# AdaptadorUSB.net
KiCad netlist of a schematic drawn in Altium Designer
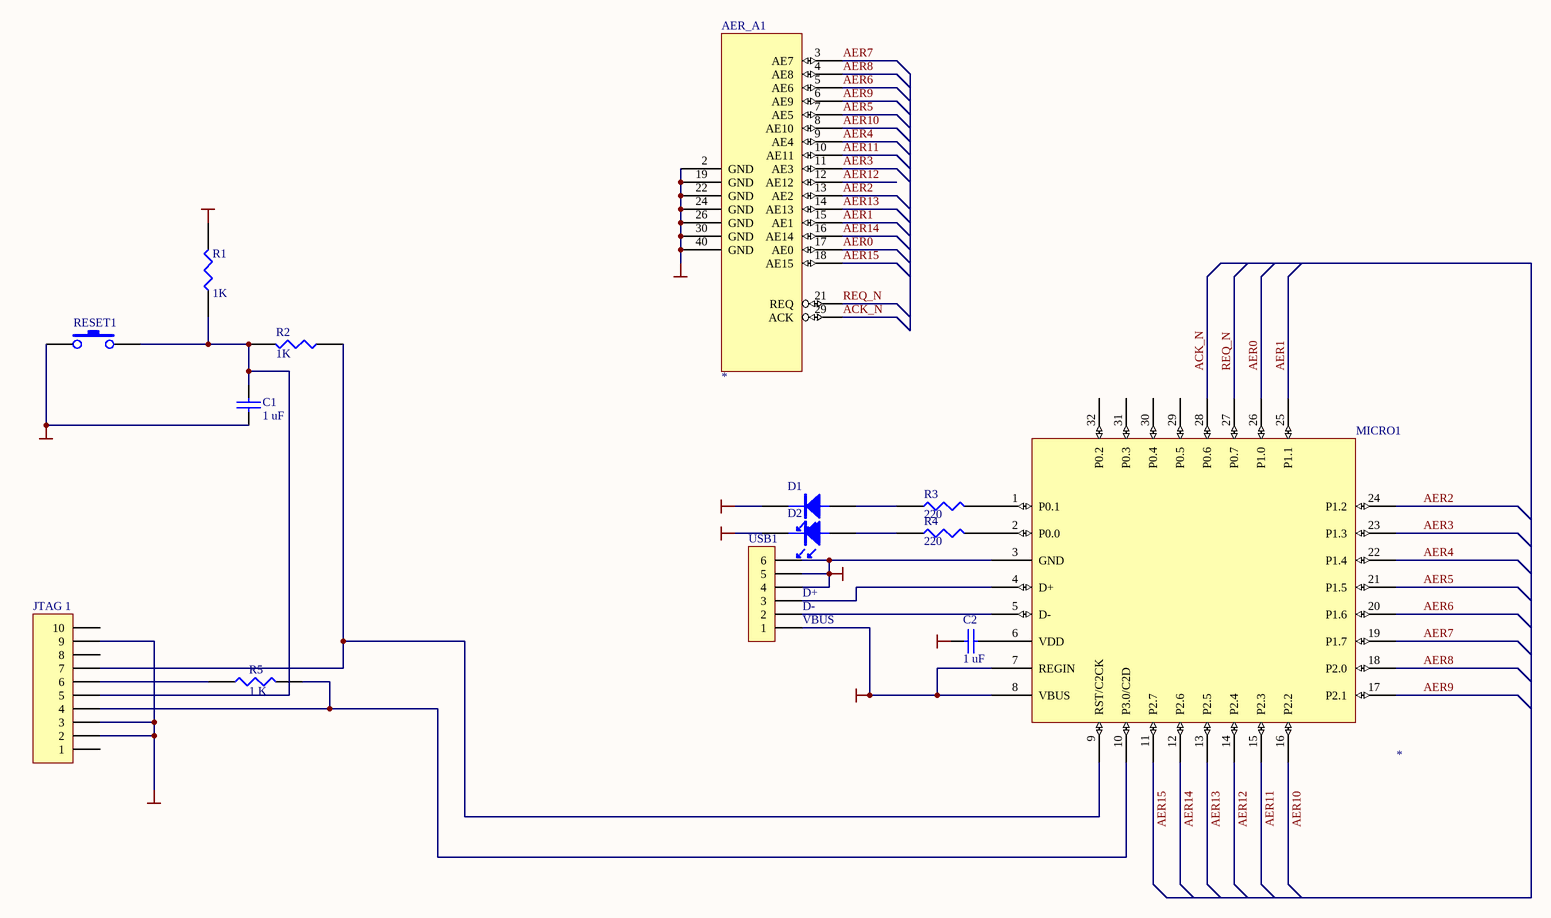
[diagram p0: AdaptadorUSB.SchDoc]

(export (version "E")
  (design (tool "Eeschema 10.0.6"))
  (components
    (comp (ref "AER_A1") (value "*") (footprint "IDC-40") (libsource (lib "Schlib1") (part "CON_AER1")))
    (comp (ref "C1")
      (value "1 uF")
      (footprint "CAP 10")
      (description "Capacitor")
      (libsource (lib "*") (part "CAP"))
    )
    (comp (ref "C2")
      (value "1 uF")
      (footprint "CAP 10")
      (description "Capacitor")
      (libsource (lib "*") (part "CAP"))
    )
    (comp (ref "D1") (value "~") (footprint "LED") (libsource (lib "*") (part "LED")))
    (comp (ref "D2") (value "~") (footprint "LED") (libsource (lib "*") (part "LED")))
    (comp (ref "JTAG 1")
      (value "~")
      (footprint "IDC-10")
      (description "Connector")
      (libsource (lib "*") (part "CON10"))
    )
    (comp (ref "MICRO1") (value "*") (footprint "LQFP-32") (libsource (lib "Schlib1") (part "C8051F320")))
    (comp (ref "R1") (value "1K") (footprint "AXIAL-0.4") (libsource (lib "*") (part "RES1")))
    (comp (ref "R2") (value "1K") (footprint "AXIAL-0.4") (libsource (lib "*") (part "RES1")))
    (comp (ref "R3") (value "220") (footprint "AXIAL-0.4") (libsource (lib "*") (part "RES1")))
    (comp (ref "R4") (value "220") (footprint "AXIAL-0.4") (libsource (lib "*") (part "RES1")))
    (comp (ref "R5") (value "1 K") (footprint "AXIAL-0.4") (libsource (lib "*") (part "RES1")))
    (comp (ref "RESET1") (value "~") (footprint "SIP-2") (libsource (lib "*") (part "SW-PB")))
    (comp (ref "USB1")
      (value "~")
      (footprint "USB_CON")
      (description "Connector")
      (libsource (lib "*") (part "CON6"))
    )
  )
  (nets
    (net (code "1") (name "/ACK_N") (class "Default")
      (node (ref "AER_A1") (pin "29") (pinfunction "ACK_29") (pintype "bidirectional"))
      (node (ref "MICRO1") (pin "28") (pinfunction "P0.6_28") (pintype "bidirectional"))
    )
    (net (code "2") (name "/AER0") (class "Default")
      (node (ref "AER_A1") (pin "17") (pinfunction "AE0_17") (pintype "bidirectional"))
      (node (ref "MICRO1") (pin "26") (pinfunction "P1.0_26") (pintype "bidirectional"))
    )
    (net (code "3") (name "/AER1") (class "Default")
      (node (ref "AER_A1") (pin "15") (pinfunction "AE1_15") (pintype "bidirectional"))
      (node (ref "MICRO1") (pin "25") (pinfunction "P1.1_25") (pintype "bidirectional"))
    )
    (net (code "4") (name "/AER2") (class "Default")
      (node (ref "AER_A1") (pin "13") (pinfunction "AE2_13") (pintype "bidirectional"))
      (node (ref "MICRO1") (pin "24") (pinfunction "P1.2_24") (pintype "bidirectional"))
    )
    (net (code "5") (name "/AER3") (class "Default")
      (node (ref "AER_A1") (pin "11") (pinfunction "AE3_11") (pintype "bidirectional"))
      (node (ref "MICRO1") (pin "23") (pinfunction "P1.3_23") (pintype "bidirectional"))
    )
    (net (code "6") (name "/AER4") (class "Default")
      (node (ref "AER_A1") (pin "9") (pinfunction "AE4_9") (pintype "bidirectional"))
      (node (ref "MICRO1") (pin "22") (pinfunction "P1.4_22") (pintype "bidirectional"))
    )
    (net (code "7") (name "/AER5") (class "Default")
      (node (ref "AER_A1") (pin "7") (pinfunction "AE5_7") (pintype "bidirectional"))
      (node (ref "MICRO1") (pin "21") (pinfunction "P1.5_21") (pintype "bidirectional"))
    )
    (net (code "8") (name "/AER6") (class "Default")
      (node (ref "AER_A1") (pin "5") (pinfunction "AE6_5") (pintype "bidirectional"))
      (node (ref "MICRO1") (pin "20") (pinfunction "P1.6_20") (pintype "bidirectional"))
    )
    (net (code "9") (name "/AER7") (class "Default")
      (node (ref "AER_A1") (pin "3") (pinfunction "AE7_3") (pintype "bidirectional"))
      (node (ref "MICRO1") (pin "19") (pinfunction "P1.7_19") (pintype "bidirectional"))
    )
    (net (code "10") (name "/AER8") (class "Default")
      (node (ref "AER_A1") (pin "4") (pinfunction "AE8_4") (pintype "bidirectional"))
      (node (ref "MICRO1") (pin "18") (pinfunction "P2.0_18") (pintype "bidirectional"))
    )
    (net (code "11") (name "/AER9") (class "Default")
      (node (ref "AER_A1") (pin "6") (pinfunction "AE9_6") (pintype "bidirectional"))
      (node (ref "MICRO1") (pin "17") (pinfunction "P2.1_17") (pintype "bidirectional"))
    )
    (net (code "12") (name "/AER10") (class "Default")
      (node (ref "AER_A1") (pin "8") (pinfunction "AE10_8") (pintype "bidirectional"))
      (node (ref "MICRO1") (pin "16") (pinfunction "P2.2_16") (pintype "bidirectional"))
    )
    (net (code "13") (name "/AER11") (class "Default")
      (node (ref "AER_A1") (pin "10") (pinfunction "AE11_10") (pintype "bidirectional"))
      (node (ref "MICRO1") (pin "15") (pinfunction "P2.3_15") (pintype "bidirectional"))
    )
    (net (code "14") (name "/AER12") (class "Default")
      (node (ref "AER_A1") (pin "12") (pinfunction "AE12_12") (pintype "bidirectional"))
      (node (ref "MICRO1") (pin "14") (pinfunction "P2.4_14") (pintype "bidirectional"))
    )
    (net (code "15") (name "/AER13") (class "Default")
      (node (ref "AER_A1") (pin "14") (pinfunction "AE13_14") (pintype "bidirectional"))
      (node (ref "MICRO1") (pin "13") (pinfunction "P2.5_13") (pintype "bidirectional"))
    )
    (net (code "16") (name "/AER14") (class "Default")
      (node (ref "AER_A1") (pin "16") (pinfunction "AE14_16") (pintype "bidirectional"))
      (node (ref "MICRO1") (pin "12") (pinfunction "P2.6_12") (pintype "bidirectional"))
    )
    (net (code "17") (name "/AER15") (class "Default")
      (node (ref "AER_A1") (pin "18") (pinfunction "AE15_18") (pintype "bidirectional"))
      (node (ref "MICRO1") (pin "11") (pinfunction "P2.7_11") (pintype "bidirectional"))
    )
    (net (code "18") (name "/REQ_N") (class "Default")
      (node (ref "AER_A1") (pin "21") (pinfunction "REQ_21") (pintype "bidirectional"))
      (node (ref "MICRO1") (pin "27") (pinfunction "P0.7_27") (pintype "bidirectional"))
    )
    (net (code "19") (name "GND") (class "Default")
      (node (ref "AER_A1") (pin "19") (pinfunction "GND_19") (pintype "power_in"))
      (node (ref "AER_A1") (pin "2") (pinfunction "GND_2") (pintype "power_in"))
      (node (ref "AER_A1") (pin "22") (pinfunction "GND_22") (pintype "power_in"))
      (node (ref "AER_A1") (pin "24") (pinfunction "GND_24") (pintype "power_in"))
      (node (ref "AER_A1") (pin "26") (pinfunction "GND_26") (pintype "power_in"))
      (node (ref "AER_A1") (pin "30") (pinfunction "GND_30") (pintype "power_in"))
      (node (ref "AER_A1") (pin "40") (pinfunction "GND_40") (pintype "power_in"))
      (node (ref "C1") (pin "2") (pinfunction "2_2") (pintype "passive"))
      (node (ref "C2") (pin "1") (pinfunction "1_1") (pintype "passive"))
      (node (ref "D1") (pin "K") (pinfunction "2_K") (pintype "passive"))
      (node (ref "D2") (pin "K") (pinfunction "2_K") (pintype "passive"))
      (node (ref "JTAG 1") (pin "2") (pinfunction "2_2") (pintype "passive"))
      (node (ref "JTAG 1") (pin "3") (pinfunction "3_3") (pintype "passive"))
      (node (ref "JTAG 1") (pin "9") (pinfunction "9_9") (pintype "passive"))
      (node (ref "MICRO1") (pin "3") (pinfunction "GND_3") (pintype "power_in"))
      (node (ref "RESET1") (pin "1") (pinfunction "1_1") (pintype "passive"))
      (node (ref "USB1") (pin "4") (pinfunction "4_4") (pintype "passive"))
      (node (ref "USB1") (pin "5") (pinfunction "5_5") (pintype "passive"))
      (node (ref "USB1") (pin "6") (pinfunction "6_6") (pintype "passive"))
    )
    (net (code "20") (name "Net-(C1-Pad1)") (class "Default")
      (node (ref "C1") (pin "1") (pinfunction "1_1") (pintype "passive"))
      (node (ref "JTAG 1") (pin "5") (pinfunction "5_5") (pintype "passive"))
      (node (ref "R1") (pin "1") (pinfunction "1_1") (pintype "passive"))
      (node (ref "R2") (pin "2") (pinfunction "2_2") (pintype "passive"))
      (node (ref "RESET1") (pin "2") (pinfunction "2_2") (pintype "passive"))
    )
    (net (code "21") (name "Net-(D1-1)") (class "Default")
      (node (ref "D1") (pin "A") (pinfunction "1_A") (pintype "passive"))
      (node (ref "R3") (pin "1") (pinfunction "1_1") (pintype "passive"))
    )
    (net (code "22") (name "Net-(D2-1)") (class "Default")
      (node (ref "D2") (pin "A") (pinfunction "1_A") (pintype "passive"))
      (node (ref "R4") (pin "1") (pinfunction "1_1") (pintype "passive"))
    )
    (net (code "23") (name "Net-(JTAG 1-Pad6)") (class "Default")
      (node (ref "JTAG 1") (pin "6") (pinfunction "6_6") (pintype "passive"))
      (node (ref "R5") (pin "1") (pinfunction "1_1") (pintype "passive"))
    )
    (net (code "24") (name "Net-(MICRO1-D+)") (class "Default")
      (node (ref "MICRO1") (pin "4") (pinfunction "D+_4") (pintype "bidirectional"))
      (node (ref "USB1") (pin "3") (pinfunction "3_3") (pintype "passive"))
    )
    (net (code "25") (name "Net-(MICRO1-D-)") (class "Default")
      (node (ref "MICRO1") (pin "5") (pinfunction "D-_5") (pintype "bidirectional"))
      (node (ref "USB1") (pin "2") (pinfunction "2_2") (pintype "passive"))
    )
    (net (code "26") (name "Net-(MICRO1-P0.0)") (class "Default")
      (node (ref "MICRO1") (pin "2") (pinfunction "P0.0_2") (pintype "bidirectional"))
      (node (ref "R4") (pin "2") (pinfunction "2_2") (pintype "passive"))
    )
    (net (code "27") (name "Net-(MICRO1-P0.1)") (class "Default")
      (node (ref "MICRO1") (pin "1") (pinfunction "P0.1_1") (pintype "bidirectional"))
      (node (ref "R3") (pin "2") (pinfunction "2_2") (pintype "passive"))
    )
    (net (code "28") (name "Net-(MICRO1-P3.0{slash}C2D)") (class "Default")
      (node (ref "JTAG 1") (pin "4") (pinfunction "4_4") (pintype "passive"))
      (node (ref "MICRO1") (pin "10") (pinfunction "P3.0/C2D_10") (pintype "bidirectional"))
      (node (ref "R5") (pin "2") (pinfunction "2_2") (pintype "passive"))
    )
    (net (code "29") (name "Net-(MICRO1-RST{slash}C2CK)") (class "Default")
      (node (ref "JTAG 1") (pin "7") (pinfunction "7_7") (pintype "passive"))
      (node (ref "MICRO1") (pin "9") (pinfunction "RST/C2CK_9") (pintype "bidirectional"))
      (node (ref "R2") (pin "1") (pinfunction "1_1") (pintype "passive"))
    )
    (net (code "30") (name "Net-(MICRO1-VDD)") (class "Default")
      (node (ref "C2") (pin "2") (pinfunction "2_2") (pintype "passive"))
      (node (ref "MICRO1") (pin "6") (pinfunction "VDD_6") (pintype "power_in"))
    )
    (net (code "31") (name "VCC_3.3V") (class "Default")
      (node (ref "MICRO1") (pin "7") (pinfunction "REGIN_7") (pintype "power_in"))
      (node (ref "MICRO1") (pin "8") (pinfunction "VBUS_8") (pintype "power_in"))
      (node (ref "R1") (pin "2") (pinfunction "2_2") (pintype "passive"))
      (node (ref "USB1") (pin "1") (pinfunction "1_1") (pintype "passive"))
    )
    (net (code "32") (name "unconnected-(JTAG 1-Pad1)") (class "Default")
      (node (ref "JTAG 1") (pin "1") (pinfunction "1_1") (pintype "passive"))
    )
    (net (code "33") (name "unconnected-(JTAG 1-Pad8)") (class "Default")
      (node (ref "JTAG 1") (pin "8") (pinfunction "8_8") (pintype "passive"))
    )
    (net (code "34") (name "unconnected-(JTAG 1-Pad10)") (class "Default")
      (node (ref "JTAG 1") (pin "10") (pinfunction "10_10") (pintype "passive"))
    )
    (net (code "35") (name "unconnected-(MICRO1-P0.2-Pad32)") (class "Default")
      (node (ref "MICRO1") (pin "32") (pinfunction "P0.2_32") (pintype "bidirectional"))
    )
    (net (code "36") (name "unconnected-(MICRO1-P0.3-Pad31)") (class "Default")
      (node (ref "MICRO1") (pin "31") (pinfunction "P0.3_31") (pintype "bidirectional"))
    )
    (net (code "37") (name "unconnected-(MICRO1-P0.4-Pad30)") (class "Default")
      (node (ref "MICRO1") (pin "30") (pinfunction "P0.4_30") (pintype "bidirectional"))
    )
    (net (code "38") (name "unconnected-(MICRO1-P0.5-Pad29)") (class "Default")
      (node (ref "MICRO1") (pin "29") (pinfunction "P0.5_29") (pintype "bidirectional"))
    )
  )
)
